# Power.net
KiCad netlist of a schematic drawn in Altium Designer
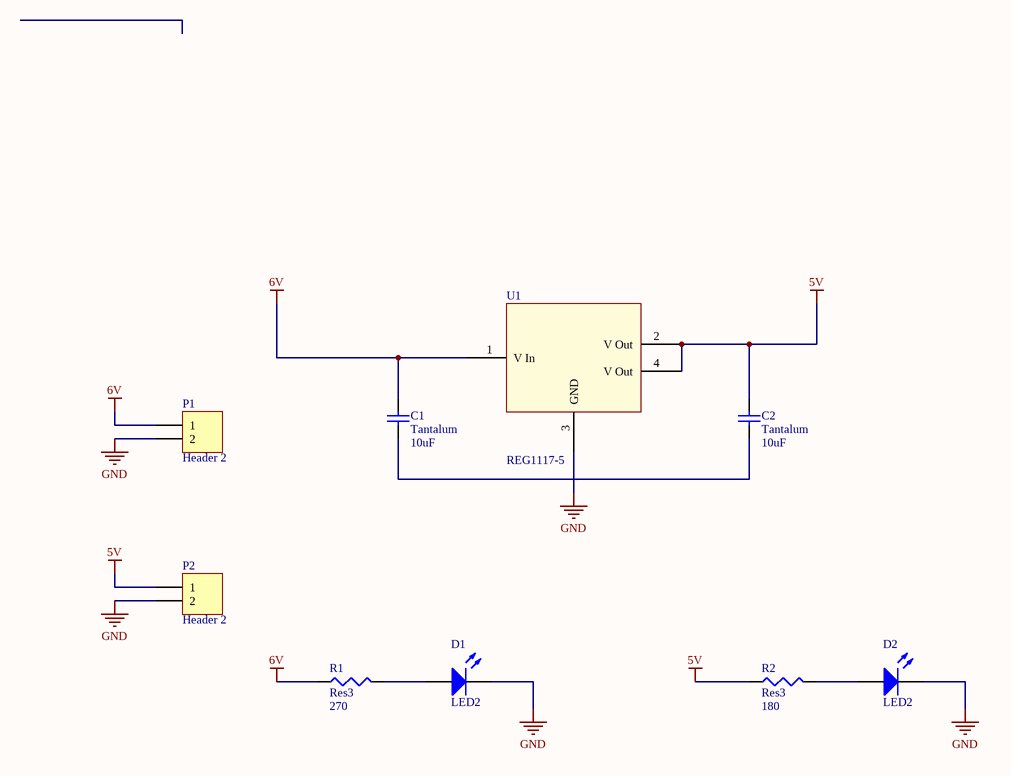
[diagram p0: Power.SchDoc]

(export (version "E")
  (design (tool "Eeschema 10.0.6"))
  (components
    (comp (ref "C1")
      (value "Tantalum")
      (footprint "C1206")
      (description "Capacitor (Semiconductor SIM Model)")
      (fields (field (name "ALTIUM_VALUE") "10uF") (field (name "PUBLISHER") "Altium Limited"))
      (libsource (lib "Miscellaneous Devices") (part "Cap Semi"))
    )
    (comp (ref "C2")
      (value "Tantalum")
      (footprint "C1206")
      (description "Capacitor (Semiconductor SIM Model)")
      (fields (field (name "ALTIUM_VALUE") "10uF") (field (name "PUBLISHER") "Altium Limited"))
      (libsource (lib "Miscellaneous Devices") (part "Cap Semi"))
    )
    (comp (ref "D1")
      (value "LED2")
      (footprint "3.2X1.6X1.1")
      (description "Typical RED, GREEN, YELLOW, AMBER GaAs LED")
      (fields (field (name "PUBLISHER") "Altium Limited"))
      (libsource (lib "Miscellaneous Devices") (part "LED2"))
    )
    (comp (ref "D2")
      (value "LED2")
      (footprint "3.2X1.6X1.1")
      (description "Typical RED, GREEN, YELLOW, AMBER GaAs LED")
      (fields (field (name "PUBLISHER") "Altium Limited"))
      (libsource (lib "Miscellaneous Devices") (part "LED2"))
    )
    (comp (ref "P1")
      (value "Header 2")
      (footprint "HDR1X2")
      (description "Header, 2-Pin")
      (fields (field (name "PUBLISHER") "Altium Limited"))
      (libsource (lib "Miscellaneous Connectors") (part "Header 2"))
    )
    (comp (ref "P2")
      (value "Header 2")
      (footprint "HDR1X2")
      (description "Header, 2-Pin")
      (fields (field (name "PUBLISHER") "Altium Limited"))
      (libsource (lib "Miscellaneous Connectors") (part "Header 2"))
    )
    (comp (ref "R1")
      (value "Res3")
      (footprint "J1-0603")
      (description "Resistor")
      (fields (field (name "ALTIUM_VALUE") "270") (field (name "PUBLISHER") "Altium Limited"))
      (libsource (lib "Miscellaneous Devices") (part "Res3"))
    )
    (comp (ref "R2")
      (value "Res3")
      (footprint "J1-0603")
      (description "Resistor")
      (fields (field (name "ALTIUM_VALUE") "180") (field (name "PUBLISHER") "Altium Limited"))
      (libsource (lib "Miscellaneous Devices") (part "Res3"))
    )
    (comp (ref "U1")
      (value "REG1117-5")
      (footprint "SOT230P710X180-4N")
      (description "REG1117-5, Voltage Regulator, 5V Out, 800mA")
      (libsource (lib "REG1117-5") (part "REG1117-5"))
    )
  )
  (nets
    (net (code "1") (name "5V") (class "Default")
      (node (ref "C2") (pin "2") (pinfunction "2_2") (pintype "passive"))
      (node (ref "P2") (pin "1") (pinfunction "1_1") (pintype "passive"))
      (node (ref "R2") (pin "1") (pinfunction "1_1") (pintype "passive"))
      (node (ref "U1") (pin "2") (pinfunction "V_Out_2") (pintype "passive"))
      (node (ref "U1") (pin "4") (pinfunction "V_Out_4") (pintype "passive"))
    )
    (net (code "2") (name "6V") (class "Default")
      (node (ref "C1") (pin "2") (pinfunction "2_2") (pintype "passive"))
      (node (ref "P1") (pin "1") (pinfunction "1_1") (pintype "passive"))
      (node (ref "R1") (pin "1") (pinfunction "1_1") (pintype "passive"))
      (node (ref "U1") (pin "1") (pinfunction "V_In_1") (pintype "passive"))
    )
    (net (code "3") (name "GND") (class "Default")
      (node (ref "D1") (pin "2") (pinfunction "K_2") (pintype "passive"))
      (node (ref "D2") (pin "2") (pinfunction "K_2") (pintype "passive"))
      (node (ref "P1") (pin "2") (pinfunction "2_2") (pintype "passive"))
      (node (ref "P2") (pin "2") (pinfunction "2_2") (pintype "passive"))
      (node (ref "U1") (pin "3") (pinfunction "GND_3") (pintype "passive"))
    )
    (net (code "4") (name "Net-(C1-Pad1)") (class "Default")
      (node (ref "C1") (pin "1") (pinfunction "1_1") (pintype "passive"))
      (node (ref "C2") (pin "1") (pinfunction "1_1") (pintype "passive"))
    )
    (net (code "5") (name "Net-(D1-A)") (class "Default")
      (node (ref "D1") (pin "1") (pinfunction "A_1") (pintype "passive"))
      (node (ref "R1") (pin "2") (pinfunction "2_2") (pintype "passive"))
    )
    (net (code "6") (name "Net-(D2-A)") (class "Default")
      (node (ref "D2") (pin "1") (pinfunction "A_1") (pintype "passive"))
      (node (ref "R2") (pin "2") (pinfunction "2_2") (pintype "passive"))
    )
  )
)
